# MCU_SCH.net
KiCad netlist of a schematic drawn in Altium Designer
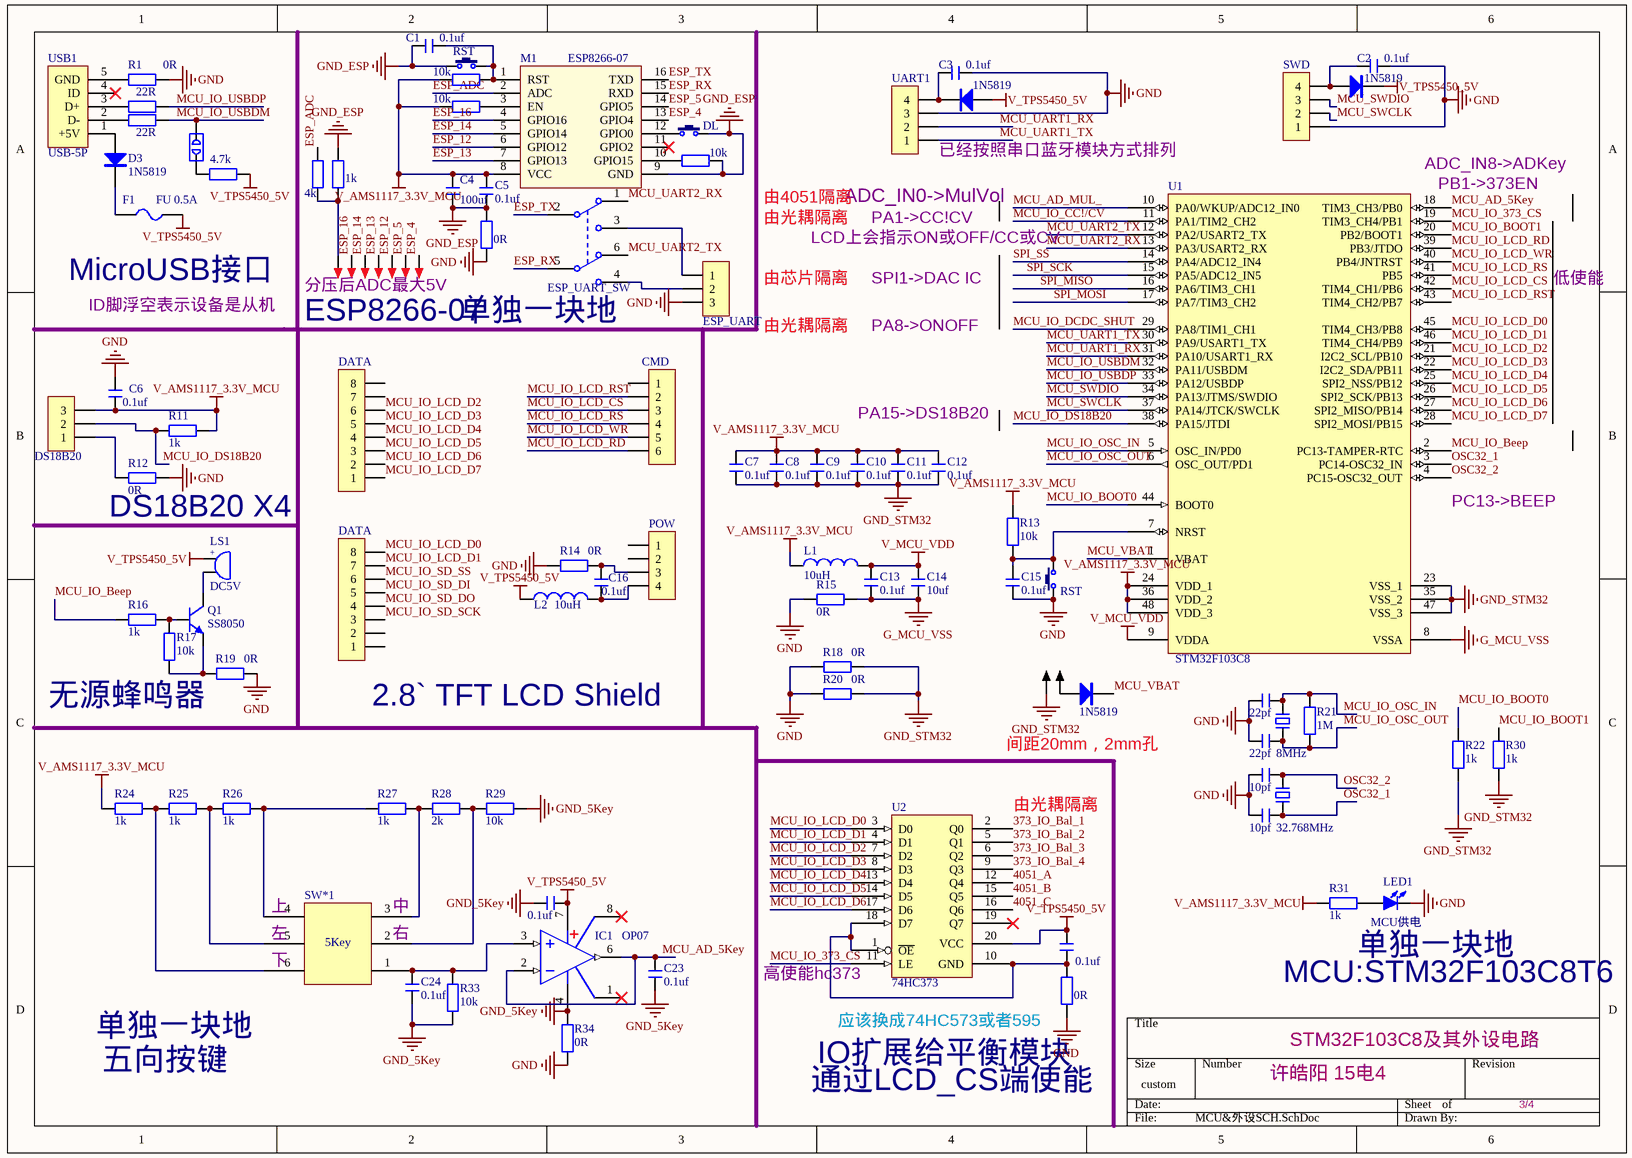
[diagram p0: MCU&外设SCH.SchDoc]

(export (version "E")
  (design (tool "Eeschema 10.0.6"))
  (components
    (comp (ref "*.")
      (value "CS")
      (footprint "HDR2.54-LI-1P")
      (description "探针焊盘")
      (libsource (lib "15.1 - 未分类器件") (part "CS"))
    )
    (comp (ref "*..")
      (value "CS")
      (footprint "HDR2.54-LI-1P")
      (description "探针焊盘")
      (libsource (lib "15.1 - 未分类器件") (part "CS"))
    )
    (comp (ref "C1")
      (value "0.1uf")
      (footprint "C 0805_M")
      (description "无极性贴片电容")
      (libsource (lib "3.1   - 电阻-电容-电感") (part "C"))
    )
    (comp (ref "C2")
      (value "0.1uf")
      (footprint "C 0805_M")
      (description "无极性贴片电容")
      (libsource (lib "3.1   - 电阻-电容-电感") (part "C"))
    )
    (comp (ref "C3")
      (value "0.1uf")
      (footprint "C 0805_M")
      (description "无极性贴片电容")
      (libsource (lib "3.1   - 电阻-电容-电感") (part "C"))
    )
    (comp (ref "C4")
      (value "100uf")
      (footprint "CD D(7343)")
      (description "无极性贴片电容")
      (libsource (lib "3.1   - 电阻-电容-电感") (part "C"))
    )
    (comp (ref "C5")
      (value "0.1uf")
      (footprint "C 0805_M")
      (description "无极性贴片电容")
      (libsource (lib "3.1   - 电阻-电容-电感") (part "C"))
    )
    (comp (ref "C6")
      (value "0.1uf")
      (footprint "C 0805_M")
      (description "无极性贴片电容")
      (libsource (lib "3.1   - 电阻-电容-电感") (part "C"))
    )
    (comp (ref "C7")
      (value "0.1uf")
      (footprint "C 0805_M")
      (description "无极性贴片电容")
      (libsource (lib "3.1   - 电阻-电容-电感") (part "C"))
    )
    (comp (ref "C8")
      (value "0.1uf")
      (footprint "C 0805_M")
      (description "无极性贴片电容")
      (libsource (lib "3.1   - 电阻-电容-电感") (part "C"))
    )
    (comp (ref "C9")
      (value "0.1uf")
      (footprint "C 0805_M")
      (description "无极性贴片电容")
      (libsource (lib "3.1   - 电阻-电容-电感") (part "C"))
    )
    (comp (ref "C10")
      (value "0.1uf")
      (footprint "C 0805_M")
      (description "无极性贴片电容")
      (libsource (lib "3.1   - 电阻-电容-电感") (part "C"))
    )
    (comp (ref "C11")
      (value "0.1uf")
      (footprint "C 0805_M")
      (description "无极性贴片电容")
      (libsource (lib "3.1   - 电阻-电容-电感") (part "C"))
    )
    (comp (ref "C12")
      (value "0.1uf")
      (footprint "C 0805_M")
      (description "无极性贴片电容")
      (libsource (lib "3.1   - 电阻-电容-电感") (part "C"))
    )
    (comp (ref "C13")
      (value "0.1uf")
      (footprint "C 0805_M")
      (description "无极性贴片电容")
      (libsource (lib "3.1   - 电阻-电容-电感") (part "C"))
    )
    (comp (ref "C14")
      (value "10uf")
      (footprint "C 0805_M")
      (description "无极性贴片电容")
      (libsource (lib "3.1   - 电阻-电容-电感") (part "C"))
    )
    (comp (ref "C15")
      (value "0.1uf")
      (footprint "C 0805_M")
      (description "无极性贴片电容")
      (libsource (lib "3.1   - 电阻-电容-电感") (part "C"))
    )
    (comp (ref "C16")
      (value "0.1uf")
      (footprint "C 0805_M")
      (description "无极性贴片电容")
      (libsource (lib "3.1   - 电阻-电容-电感") (part "C"))
    )
    (comp (ref "C17")
      (value "22pf")
      (footprint "C 0805_M")
      (description "无极性贴片电容")
      (libsource (lib "3.1   - 电阻-电容-电感") (part "C"))
    )
    (comp (ref "C18")
      (value "22pf")
      (footprint "C 0805_M")
      (description "无极性贴片电容")
      (libsource (lib "3.1   - 电阻-电容-电感") (part "C"))
    )
    (comp (ref "C19")
      (value "10pf")
      (footprint "C 0805_M")
      (description "无极性贴片电容")
      (libsource (lib "3.1   - 电阻-电容-电感") (part "C"))
    )
    (comp (ref "C20")
      (value "10pf")
      (footprint "C 0805_M")
      (description "无极性贴片电容")
      (libsource (lib "3.1   - 电阻-电容-电感") (part "C"))
    )
    (comp (ref "C21")
      (value "0.1uf")
      (footprint "C 0805_M")
      (description "无极性贴片电容")
      (libsource (lib "3.1   - 电阻-电容-电感") (part "C"))
    )
    (comp (ref "C22")
      (value "0.1uf")
      (footprint "C 0805_M")
      (description "无极性贴片电容")
      (libsource (lib "3.1   - 电阻-电容-电感") (part "C"))
    )
    (comp (ref "C23")
      (value "0.1uf")
      (footprint "C 0805_M")
      (description "无极性贴片电容")
      (libsource (lib "3.1   - 电阻-电容-电感") (part "C"))
    )
    (comp (ref "C24")
      (value "0.1uf")
      (footprint "C 0805_M")
      (description "无极性贴片电容")
      (libsource (lib "3.1   - 电阻-电容-电感") (part "C"))
    )
    (comp (ref "D1")
      (value "1N5819")
      (footprint "SOD-123")
      (description "肖特基二极管")
      (libsource (lib "8.1   - 二极管-整流桥") (part "1N5819"))
    )
    (comp (ref "D2")
      (value "1N5819")
      (footprint "SOD-123")
      (description "肖特基二极管")
      (libsource (lib "8.1   - 二极管-整流桥") (part "1N5819"))
    )
    (comp (ref "D2.")
      (value "1N5819")
      (footprint "SOD-123")
      (description "肖特基二极管")
      (libsource (lib "8.1   - 二极管-整流桥") (part "1N5819"))
    )
    (comp (ref "D3")
      (value "1N5819")
      (footprint "SOD-123")
      (description "肖特基二极管")
      (libsource (lib "8.1   - 二极管-整流桥") (part "1N5819"))
    )
    (comp (ref "DE1")
      (value "1")
      (footprint "DEBUG_B")
      (description "调试断点焊盘")
      (libsource (lib "15.1 - 未分类器件") (part "DEBUG"))
    )
    (comp (ref "F1")
      (value "FU 0.5A")
      (footprint "FU 1206")
      (description "贴片保险丝")
      (libsource (lib "10.1 - 保险丝-晶振") (part "FU"))
    )
    (comp (ref "IC1")
      (value "OP07")
      (footprint "SOP8_N")
      (description "单路精密运放")
      (libsource (lib "1.5   - 运放-功放") (part "OP07"))
    )
    (comp (ref "JP1")
      (value "SWD")
      (footprint "HDR2.54-LI-4P")
      (description "4P接插件")
      (libsource (lib "") (part "Header 4_1"))
    )
    (comp (ref "JP2")
      (value "UART1")
      (footprint "HDR2.54-LI-4P")
      (description "4P接插件")
      (libsource (lib "") (part "Header 4_1"))
    )
    (comp (ref "JP3")
      (value "ESP_UART")
      (footprint "HDR2.54-LI-3P")
      (description "3P接插件")
      (libsource (lib "") (part "Header 3_1"))
    )
    (comp (ref "JP4")
      (value "DS18B20")
      (footprint "HDR2.54-LI-3P")
      (description "3P接插件")
      (libsource (lib "4.6   - 接插件-脚距2.54") (part "Header 3"))
    )
    (comp (ref "JP5")
      (value "CMD")
      (footprint "HDR2.54-M-LI-6P")
      (description "6P接插件")
      (libsource (lib "4.6   - 接插件-脚距2.54") (part "Header 6"))
    )
    (comp (ref "JP6")
      (value "DATA")
      (footprint "HDR2.54-M-LI-8P")
      (description "8P接插件")
      (libsource (lib "4.6   - 接插件-脚距2.54") (part "Header 8"))
    )
    (comp (ref "JP6.")
      (value "DATA")
      (footprint "HDR2.54-M-LI-8P")
      (description "8P接插件")
      (libsource (lib "4.6   - 接插件-脚距2.54") (part "Header 8"))
    )
    (comp (ref "JP7")
      (value "POW")
      (footprint "HDR2.54-M-LI-4P")
      (description "4P接插件")
      (libsource (lib "4.6   - 接插件-脚距2.54") (part "Header 4"))
    )
    (comp (ref "L1")
      (value "10uH")
      (footprint "L 0805_M")
      (description "小功率贴片电感")
      (libsource (lib "3.1   - 电阻-电容-电感") (part "L"))
    )
    (comp (ref "L2")
      (value "10uH")
      (footprint "L 0805_M")
      (description "小功率贴片电感")
      (libsource (lib "3.1   - 电阻-电容-电感") (part "L"))
    )
    (comp (ref "LED1")
      (value "MCU供电")
      (footprint "LED 0805G")
      (description "贴片LED")
      (libsource (lib "9.1   - LED") (part "LED-SMD"))
    )
    (comp (ref "LS1")
      (value "DC5V")
      (footprint "BEEP 7.6X12X7.5")
      (description "蜂鸣器")
      (libsource (lib "15.1 - 未分类器件") (part "BEEP"))
    )
    (comp (ref "M1")
      (value "ESP8266-07")
      (footprint "ESP-07")
      (description "串口 WIFI模块，ESP-07")
      (libsource (lib "13.1 - 模块") (part "ESP8266-07"))
    )
    (comp (ref "Q1")
      (value "SS8050")
      (footprint "SOT23-3M")
      (description "高频放大-NPN型")
      (libsource (lib "6.2   - 三极管") (part "8050-SMD"))
    )
    (comp (ref "R1")
      (value "0R")
      (footprint "R 0805_M")
      (description "贴片电阻")
      (libsource (lib "3.1   - 电阻-电容-电感") (part "R"))
    )
    (comp (ref "R2")
      (value "10k")
      (footprint "R 0805_M")
      (description "贴片电阻")
      (libsource (lib "3.1   - 电阻-电容-电感") (part "R"))
    )
    (comp (ref "R3")
      (value "22R")
      (footprint "R 0805_M")
      (description "贴片电阻")
      (libsource (lib "3.1   - 电阻-电容-电感") (part "R"))
    )
    (comp (ref "R4")
      (value "10k")
      (footprint "R 0805_M")
      (description "贴片电阻")
      (libsource (lib "3.1   - 电阻-电容-电感") (part "R"))
    )
    (comp (ref "R5")
      (value "22R")
      (footprint "R 0805_M")
      (description "贴片电阻")
      (libsource (lib "3.1   - 电阻-电容-电感") (part "R"))
    )
    (comp (ref "R6")
      (value "10k")
      (footprint "R 0805_M")
      (description "贴片电阻")
      (libsource (lib "3.1   - 电阻-电容-电感") (part "R"))
    )
    (comp (ref "R7")
      (value "4.7k")
      (footprint "R 0805_M")
      (description "贴片电阻")
      (libsource (lib "3.1   - 电阻-电容-电感") (part "R"))
    )
    (comp (ref "R8")
      (value "4k")
      (footprint "R 0805_M")
      (description "贴片电阻")
      (libsource (lib "3.1   - 电阻-电容-电感") (part "R"))
    )
    (comp (ref "R9")
      (value "1k")
      (footprint "R 0805_M")
      (description "贴片电阻")
      (libsource (lib "3.1   - 电阻-电容-电感") (part "R"))
    )
    (comp (ref "R10")
      (value "0R")
      (footprint "R 0805_M")
      (description "贴片电阻")
      (libsource (lib "3.1   - 电阻-电容-电感") (part "R"))
    )
    (comp (ref "R11")
      (value "1k")
      (footprint "R 0805_M")
      (description "贴片电阻")
      (libsource (lib "3.1   - 电阻-电容-电感") (part "R"))
    )
    (comp (ref "R12")
      (value "0R")
      (footprint "R 0805_M")
      (description "贴片电阻")
      (libsource (lib "3.1   - 电阻-电容-电感") (part "R"))
    )
    (comp (ref "R13")
      (value "10k")
      (footprint "R 0805_M")
      (description "贴片电阻")
      (libsource (lib "3.1   - 电阻-电容-电感") (part "R"))
    )
    (comp (ref "R14")
      (value "0R")
      (footprint "R 0805_M")
      (description "贴片电阻")
      (libsource (lib "3.1   - 电阻-电容-电感") (part "R"))
    )
    (comp (ref "R15")
      (value "0R")
      (footprint "R 0805_M")
      (description "贴片电阻")
      (libsource (lib "3.1   - 电阻-电容-电感") (part "R"))
    )
    (comp (ref "R16")
      (value "1k")
      (footprint "R 0805_M")
      (description "贴片电阻")
      (libsource (lib "3.1   - 电阻-电容-电感") (part "R"))
    )
    (comp (ref "R17")
      (value "10k")
      (footprint "R 0805_M")
      (description "贴片电阻")
      (libsource (lib "3.1   - 电阻-电容-电感") (part "R"))
    )
    (comp (ref "R18")
      (value "0R")
      (footprint "R 0805_M")
      (description "贴片电阻")
      (libsource (lib "3.1   - 电阻-电容-电感") (part "R"))
    )
    (comp (ref "R19")
      (value "0R")
      (footprint "R 0805_M")
      (description "贴片电阻")
      (libsource (lib "3.1   - 电阻-电容-电感") (part "R"))
    )
    (comp (ref "R20")
      (value "0R")
      (footprint "R 0805_M")
      (description "贴片电阻")
      (libsource (lib "3.1   - 电阻-电容-电感") (part "R"))
    )
    (comp (ref "R21")
      (value "1M")
      (footprint "R 0805_M")
      (description "贴片电阻")
      (libsource (lib "3.1   - 电阻-电容-电感") (part "R"))
    )
    (comp (ref "R22")
      (value "1k")
      (footprint "R 0805_M")
      (description "贴片电阻")
      (libsource (lib "3.1   - 电阻-电容-电感") (part "R"))
    )
    (comp (ref "R24")
      (value "1k")
      (footprint "R 0805_M")
      (description "贴片电阻")
      (libsource (lib "3.1   - 电阻-电容-电感") (part "R"))
    )
    (comp (ref "R25")
      (value "1k")
      (footprint "R 0805_M")
      (description "贴片电阻")
      (libsource (lib "3.1   - 电阻-电容-电感") (part "R"))
    )
    (comp (ref "R26")
      (value "1k")
      (footprint "R 0805_M")
      (description "贴片电阻")
      (libsource (lib "3.1   - 电阻-电容-电感") (part "R"))
    )
    (comp (ref "R27")
      (value "1k")
      (footprint "R 0805_M")
      (description "贴片电阻")
      (libsource (lib "3.1   - 电阻-电容-电感") (part "R"))
    )
    (comp (ref "R28")
      (value "2k")
      (footprint "R 0805_M")
      (description "贴片电阻")
      (libsource (lib "3.1   - 电阻-电容-电感") (part "R"))
    )
    (comp (ref "R29")
      (value "10k")
      (footprint "R 0805_M")
      (description "贴片电阻")
      (libsource (lib "3.1   - 电阻-电容-电感") (part "R"))
    )
    (comp (ref "R30")
      (value "1k")
      (footprint "R 0805_M")
      (description "贴片电阻")
      (libsource (lib "3.1   - 电阻-电容-电感") (part "R"))
    )
    (comp (ref "R31")
      (value "1k")
      (footprint "R 0805_M")
      (description "贴片电阻")
      (libsource (lib "3.1   - 电阻-电容-电感") (part "R"))
    )
    (comp (ref "R32")
      (value "0R")
      (footprint "R 0805_M")
      (description "贴片电阻")
      (libsource (lib "3.1   - 电阻-电容-电感") (part "R"))
    )
    (comp (ref "R33")
      (value "10k")
      (footprint "R 0805_M")
      (description "贴片电阻")
      (libsource (lib "3.1   - 电阻-电容-电感") (part "R"))
    )
    (comp (ref "R34")
      (value "0R")
      (footprint "R 0805_M")
      (description "贴片电阻")
      (libsource (lib "3.1   - 电阻-电容-电感") (part "R"))
    )
    (comp (ref "S.")
      (value "ESP_UART_SW")
      (footprint "SK-22D02")
      (description "2路波动开关")
      (libsource (lib "5.1   - 按键-开关") (part "SSW-2P"))
    )
    (comp (ref "SW*1")
      (value "5Key")
      (footprint "TSW 10x10x9-5Key-LS")
      (libsource (lib "IC_temp") (part "6"))
    )
    (comp (ref "SW1")
      (value "RST")
      (footprint "TSW SMD-3*6*2.5")
      (description "3x6轻触开关")
      (libsource (lib "5.1   - 按键-开关") (part "TSW 3x6"))
    )
    (comp (ref "SW2")
      (value "DL")
      (footprint "TSW SMD-3*6*2.5")
      (description "3x6轻触开关")
      (libsource (lib "5.1   - 按键-开关") (part "TSW 3x6"))
    )
    (comp (ref "SW3")
      (value "RST")
      (footprint "TSW SMD-3*6*2.5")
      (description "3x6轻触开关")
      (libsource (lib "") (part "TSW 3x6_1"))
    )
    (comp (ref "TP1")
      (value "..")
      (footprint "TEST 1")
      (description "测试点")
      (libsource (lib "15.1 - 未分类器件") (part "TEST"))
    )
    (comp (ref "TP2")
      (value "..")
      (footprint "TEST 1")
      (description "测试点")
      (libsource (lib "15.1 - 未分类器件") (part "TEST"))
    )
    (comp (ref "TP3")
      (value "..")
      (footprint "TEST 1")
      (description "测试点")
      (libsource (lib "15.1 - 未分类器件") (part "TEST"))
    )
    (comp (ref "TP4")
      (value "..")
      (footprint "TEST 1")
      (description "测试点")
      (libsource (lib "15.1 - 未分类器件") (part "TEST"))
    )
    (comp (ref "TP5")
      (value "..")
      (footprint "TEST 1")
      (description "测试点")
      (libsource (lib "15.1 - 未分类器件") (part "TEST"))
    )
    (comp (ref "TP6")
      (value "..")
      (footprint "TEST 1")
      (description "测试点")
      (libsource (lib "15.1 - 未分类器件") (part "TEST"))
    )
    (comp (ref "TP7")
      (value "..")
      (footprint "TEST 1")
      (description "测试点")
      (libsource (lib "15.1 - 未分类器件") (part "TEST"))
    )
    (comp (ref "U1")
      (value "STM32F103C8")
      (footprint "LQFP48 7X7_N")
      (description "Flaah:64/RAM:20/IO:36")
      (libsource (lib "2.1   - STM32系列单片机") (part "STM32F103C8"))
    )
    (comp (ref "U2") (value "74HC373") (footprint "SOP20_N") (libsource (lib "逻辑门器件") (part "74HC373")))
    (comp (ref "USB1")
      (value "USB-5P")
      (footprint "USB-MICRO_E")
      (description "微型USB母座")
      (libsource (lib "4.1   - 接口类") (part "USB-5P"))
    )
    (comp (ref "X1")
      (value "8MHz")
      (footprint "OSC HC-49S")
      (description "2脚无源脚晶振")
      (libsource (lib "10.1 - 保险丝-晶振") (part "XTAL-2P"))
    )
    (comp (ref "X2")
      (value "32.768MHz")
      (footprint "OSC-3x8-LI")
      (description "2脚无源脚晶振")
      (libsource (lib "10.1 - 保险丝-晶振") (part "XTAL-2P"))
    )
  )
  (nets
    (net (code "1") (name "/373_IO_Bal_1") (class "Default")
      (node (ref "U2") (pin "2") (pinfunction "Q0_2") (pintype "tri_state"))
    )
    (net (code "2") (name "/373_IO_Bal_2") (class "Default")
      (node (ref "U2") (pin "5") (pinfunction "Q1_5") (pintype "tri_state"))
    )
    (net (code "3") (name "/373_IO_Bal_3") (class "Default")
      (node (ref "U2") (pin "6") (pinfunction "Q2_6") (pintype "tri_state"))
    )
    (net (code "4") (name "/373_IO_Bal_4") (class "Default")
      (node (ref "U2") (pin "9") (pinfunction "Q3_9") (pintype "tri_state"))
    )
    (net (code "5") (name "/4051_A") (class "Default")
      (node (ref "U2") (pin "12") (pinfunction "Q4_12") (pintype "tri_state"))
    )
    (net (code "6") (name "/4051_B") (class "Default")
      (node (ref "U2") (pin "15") (pinfunction "Q5_15") (pintype "tri_state"))
    )
    (net (code "7") (name "/4051_C") (class "Default")
      (node (ref "U2") (pin "16") (pinfunction "Q6_16") (pintype "tri_state"))
    )
    (net (code "8") (name "/ESP_4") (class "Default")
      (node (ref "M1") (pin "13") (pinfunction "GPIO4_13") (pintype "passive"))
      (node (ref "TP7") (pin "1") (pinfunction "1_1") (pintype "passive"))
    )
    (net (code "9") (name "/ESP_5") (class "Default")
      (node (ref "M1") (pin "14") (pinfunction "GPIO5_14") (pintype "passive"))
      (node (ref "TP6") (pin "1") (pinfunction "1_1") (pintype "passive"))
    )
    (net (code "10") (name "/ESP_12") (class "Default")
      (node (ref "M1") (pin "6") (pinfunction "GPIO12_6") (pintype "passive"))
      (node (ref "TP5") (pin "1") (pinfunction "1_1") (pintype "passive"))
    )
    (net (code "11") (name "/ESP_13") (class "Default")
      (node (ref "M1") (pin "7") (pinfunction "GPIO13_7") (pintype "passive"))
      (node (ref "TP4") (pin "1") (pinfunction "1_1") (pintype "passive"))
    )
    (net (code "12") (name "/ESP_14") (class "Default")
      (node (ref "M1") (pin "5") (pinfunction "GPIO14_5") (pintype "passive"))
      (node (ref "TP3") (pin "1") (pinfunction "1_1") (pintype "passive"))
    )
    (net (code "13") (name "/ESP_16") (class "Default")
      (node (ref "M1") (pin "4") (pinfunction "GPIO16_4") (pintype "passive"))
      (node (ref "TP2") (pin "1") (pinfunction "1_1") (pintype "passive"))
    )
    (net (code "14") (name "/ESP_ADC") (class "Default")
      (node (ref "M1") (pin "2") (pinfunction "ADC_2") (pintype "passive"))
      (node (ref "R8") (pin "2") (pinfunction "2_2") (pintype "passive"))
    )
    (net (code "15") (name "/ESP_RX") (class "Default")
      (node (ref "M1") (pin "15") (pinfunction "RXD_15") (pintype "passive"))
      (node (ref "S.") (pin "5") (pinfunction "5_5") (pintype "passive"))
    )
    (net (code "16") (name "/ESP_TX") (class "Default")
      (node (ref "M1") (pin "16") (pinfunction "TXD_16") (pintype "passive"))
      (node (ref "S.") (pin "2") (pinfunction "2_2") (pintype "passive"))
    )
    (net (code "17") (name "/MCU_AD_5Key") (class "Default")
      (node (ref "C23") (pin "2") (pinfunction "2_2") (pintype "passive"))
      (node (ref "IC1") (pin "2") (pinfunction "IN-_2") (pintype "input"))
      (node (ref "IC1") (pin "6") (pinfunction "OUT_6") (pintype "output"))
      (node (ref "U1") (pin "18") (pinfunction "TIM3_CH3/PB0_18") (pintype "bidirectional"))
    )
    (net (code "18") (name "/MCU_AD_MUL_") (class "Default")
      (node (ref "U1") (pin "10") (pinfunction "PA0/WKUP/ADC12_IN0_10") (pintype "bidirectional"))
    )
    (net (code "19") (name "/MCU_IO_373_CS") (class "Default")
      (node (ref "U1") (pin "19") (pinfunction "TIM3_CH4/PB1_19") (pintype "bidirectional"))
      (node (ref "U2") (pin "11") (pinfunction "LE_11") (pintype "input"))
    )
    (net (code "20") (name "/MCU_IO_BOOT0") (class "Default")
      (node (ref "R22") (pin "2") (pinfunction "2_2") (pintype "passive"))
      (node (ref "U1") (pin "44") (pinfunction "BOOT0_44") (pintype "input"))
    )
    (net (code "21") (name "/MCU_IO_BOOT1") (class "Default")
      (node (ref "R30") (pin "2") (pinfunction "2_2") (pintype "passive"))
      (node (ref "U1") (pin "20") (pinfunction "PB2/BOOT1_20") (pintype "bidirectional"))
    )
    (net (code "22") (name "/MCU_IO_Beep") (class "Default")
      (node (ref "R16") (pin "2") (pinfunction "2_2") (pintype "passive"))
      (node (ref "U1") (pin "2") (pinfunction "PC13-TAMPER-RTC_2") (pintype "bidirectional"))
    )
    (net (code "23") (name "/MCU_IO_CC!{slash}CV") (class "Default")
      (node (ref "U1") (pin "11") (pinfunction "PA1/TIM2_CH2_11") (pintype "bidirectional"))
    )
    (net (code "24") (name "/MCU_IO_DCDC_SHUT") (class "Default")
      (node (ref "U1") (pin "29") (pinfunction "PA8/TIM1_CH1_29") (pintype "bidirectional"))
    )
    (net (code "25") (name "/MCU_IO_DS18B20") (class "Default")
      (node (ref "JP4") (pin "2") (pinfunction "2_2") (pintype "passive"))
      (node (ref "R11") (pin "1") (pinfunction "1_1") (pintype "passive"))
      (node (ref "U1") (pin "38") (pinfunction "PA15/JTDI_38") (pintype "bidirectional"))
    )
    (net (code "26") (name "/MCU_IO_LCD_CS") (class "Default")
      (node (ref "JP5") (pin "3") (pinfunction "3_3") (pintype "passive"))
      (node (ref "U1") (pin "42") (pinfunction "TIM4_CH1/PB6_42") (pintype "bidirectional"))
    )
    (net (code "27") (name "/MCU_IO_LCD_D0") (class "Default")
      (node (ref "JP6.") (pin "8") (pinfunction "8_8") (pintype "passive"))
      (node (ref "U1") (pin "45") (pinfunction "TIM4_CH3/PB8_45") (pintype "bidirectional"))
      (node (ref "U2") (pin "3") (pinfunction "D0_3") (pintype "input"))
    )
    (net (code "28") (name "/MCU_IO_LCD_D1") (class "Default")
      (node (ref "JP6.") (pin "7") (pinfunction "7_7") (pintype "passive"))
      (node (ref "U1") (pin "46") (pinfunction "TIM4_CH4/PB9_46") (pintype "bidirectional"))
      (node (ref "U2") (pin "4") (pinfunction "D1_4") (pintype "input"))
    )
    (net (code "29") (name "/MCU_IO_LCD_D2") (class "Default")
      (node (ref "JP6") (pin "6") (pinfunction "6_6") (pintype "passive"))
      (node (ref "U1") (pin "21") (pinfunction "I2C2_SCL/PB10_21") (pintype "bidirectional"))
      (node (ref "U2") (pin "7") (pinfunction "D2_7") (pintype "input"))
    )
    (net (code "30") (name "/MCU_IO_LCD_D3") (class "Default")
      (node (ref "JP6") (pin "5") (pinfunction "5_5") (pintype "passive"))
      (node (ref "U1") (pin "22") (pinfunction "I2C2_SDA/PB11_22") (pintype "bidirectional"))
      (node (ref "U2") (pin "8") (pinfunction "D3_8") (pintype "input"))
    )
    (net (code "31") (name "/MCU_IO_LCD_D4") (class "Default")
      (node (ref "JP6") (pin "4") (pinfunction "4_4") (pintype "passive"))
      (node (ref "U1") (pin "25") (pinfunction "SPI2_NSS/PB12_25") (pintype "bidirectional"))
      (node (ref "U2") (pin "13") (pinfunction "D4_13") (pintype "input"))
    )
    (net (code "32") (name "/MCU_IO_LCD_D5") (class "Default")
      (node (ref "JP6") (pin "3") (pinfunction "3_3") (pintype "passive"))
      (node (ref "U1") (pin "26") (pinfunction "SPI2_SCK/PB13_26") (pintype "bidirectional"))
      (node (ref "U2") (pin "14") (pinfunction "D5_14") (pintype "input"))
    )
    (net (code "33") (name "/MCU_IO_LCD_D6") (class "Default")
      (node (ref "JP6") (pin "2") (pinfunction "2_2") (pintype "passive"))
      (node (ref "U1") (pin "27") (pinfunction "SPI2_MISO/PB14_27") (pintype "bidirectional"))
      (node (ref "U2") (pin "17") (pinfunction "D6_17") (pintype "input"))
    )
    (net (code "34") (name "/MCU_IO_LCD_D7") (class "Default")
      (node (ref "JP6") (pin "1") (pinfunction "1_1") (pintype "passive"))
      (node (ref "U1") (pin "28") (pinfunction "SPI2_MOSI/PB15_28") (pintype "bidirectional"))
    )
    (net (code "35") (name "/MCU_IO_LCD_RD") (class "Default")
      (node (ref "JP5") (pin "6") (pinfunction "6_6") (pintype "passive"))
      (node (ref "U1") (pin "39") (pinfunction "PB3/JTDO_39") (pintype "bidirectional"))
    )
    (net (code "36") (name "/MCU_IO_LCD_RS") (class "Default")
      (node (ref "JP5") (pin "4") (pinfunction "4_4") (pintype "passive"))
      (node (ref "U1") (pin "41") (pinfunction "PB5_41") (pintype "bidirectional"))
    )
    (net (code "37") (name "/MCU_IO_LCD_RST") (class "Default")
      (node (ref "JP5") (pin "2") (pinfunction "2_2") (pintype "passive"))
      (node (ref "U1") (pin "43") (pinfunction "TIM4_CH2/PB7_43") (pintype "bidirectional"))
    )
    (net (code "38") (name "/MCU_IO_LCD_WR") (class "Default")
      (node (ref "JP5") (pin "5") (pinfunction "5_5") (pintype "passive"))
      (node (ref "U1") (pin "40") (pinfunction "PB4/JNTRST_40") (pintype "bidirectional"))
    )
    (net (code "39") (name "/MCU_IO_OSC_IN") (class "Default")
      (node (ref "C17") (pin "1") (pinfunction "1_1") (pintype "passive"))
      (node (ref "R21") (pin "1") (pinfunction "1_1") (pintype "passive"))
      (node (ref "U1") (pin "5") (pinfunction "OSC_IN/PD0_5") (pintype "input"))
      (node (ref "X1") (pin "2") (pinfunction "2_2") (pintype "passive"))
    )
    (net (code "40") (name "/MCU_IO_OSC_OUT") (class "Default")
      (node (ref "C18") (pin "1") (pinfunction "1_1") (pintype "passive"))
      (node (ref "R21") (pin "2") (pinfunction "2_2") (pintype "passive"))
      (node (ref "U1") (pin "6") (pinfunction "OSC_OUT/PD1_6") (pintype "output"))
      (node (ref "X1") (pin "1") (pinfunction "1_1") (pintype "passive"))
    )
    (net (code "41") (name "/MCU_IO_SD_DI") (class "Default")
      (node (ref "JP6.") (pin "5") (pinfunction "5_5") (pintype "passive"))
    )
    (net (code "42") (name "/MCU_IO_SD_DO") (class "Default")
      (node (ref "JP6.") (pin "4") (pinfunction "4_4") (pintype "passive"))
    )
    (net (code "43") (name "/MCU_IO_SD_SCK") (class "Default")
      (node (ref "JP6.") (pin "3") (pinfunction "3_3") (pintype "passive"))
    )
    (net (code "44") (name "/MCU_IO_SD_SS") (class "Default")
      (node (ref "JP6.") (pin "6") (pinfunction "6_6") (pintype "passive"))
    )
    (net (code "45") (name "/MCU_IO_USBDM") (class "Default")
      (node (ref "DE1") (pin "2") (pinfunction "2_2") (pintype "passive"))
      (node (ref "R5") (pin "1") (pinfunction "1_1") (pintype "passive"))
      (node (ref "U1") (pin "32") (pinfunction "PA11/USBDM_32") (pintype "bidirectional"))
    )
    (net (code "46") (name "/MCU_IO_USBDP") (class "Default")
      (node (ref "R3") (pin "1") (pinfunction "1_1") (pintype "passive"))
      (node (ref "U1") (pin "33") (pinfunction "PA12/USBDP_33") (pintype "bidirectional"))
    )
    (net (code "47") (name "/MCU_SWCLK") (class "Default")
      (node (ref "JP1") (pin "2") (pinfunction "2_2") (pintype "passive"))
      (node (ref "U1") (pin "37") (pinfunction "PA14/JTCK/SWCLK_37") (pintype "bidirectional"))
    )
    (net (code "48") (name "/MCU_SWDIO") (class "Default")
      (node (ref "JP1") (pin "3") (pinfunction "3_3") (pintype "passive"))
      (node (ref "U1") (pin "34") (pinfunction "PA13/JTMS/SWDIO_34") (pintype "bidirectional"))
    )
    (net (code "49") (name "/MCU_UART1_RX") (class "Default")
      (node (ref "JP2") (pin "2") (pinfunction "2_2") (pintype "passive"))
      (node (ref "U1") (pin "31") (pinfunction "PA10/USART1_RX_31") (pintype "bidirectional"))
    )
    (net (code "50") (name "/MCU_UART1_TX") (class "Default")
      (node (ref "JP2") (pin "1") (pinfunction "1_1") (pintype "passive"))
      (node (ref "U1") (pin "30") (pinfunction "PA9/USART1_TX_30") (pintype "bidirectional"))
    )
    (net (code "51") (name "/MCU_UART2_RX") (class "Default")
      (node (ref "S.") (pin "1") (pinfunction "1_1") (pintype "passive"))
      (node (ref "U1") (pin "13") (pinfunction "PA3/USART2_RX_13") (pintype "bidirectional"))
    )
    (net (code "52") (name "/MCU_UART2_TX") (class "Default")
      (node (ref "S.") (pin "6") (pinfunction "6_6") (pintype "passive"))
      (node (ref "U1") (pin "12") (pinfunction "PA2/USART2_TX_12") (pintype "bidirectional"))
    )
    (net (code "53") (name "/MCU_VBAT") (class "Default")
      (node (ref "D2.") (pin "2") (pinfunction "K_2") (pintype "passive"))
      (node (ref "U1") (pin "1") (pinfunction "VBAT_1") (pintype "power_in"))
    )
    (net (code "54") (name "/OSC32_1") (class "Default")
      (node (ref "C20") (pin "1") (pinfunction "1_1") (pintype "passive"))
      (node (ref "U1") (pin "3") (pinfunction "PC14-OSC32_IN_3") (pintype "bidirectional"))
      (node (ref "X2") (pin "1") (pinfunction "1_1") (pintype "passive"))
    )
    (net (code "55") (name "/OSC32_2") (class "Default")
      (node (ref "C19") (pin "1") (pinfunction "1_1") (pintype "passive"))
      (node (ref "U1") (pin "4") (pinfunction "PC15-OSC32_OUT_4") (pintype "bidirectional"))
      (node (ref "X2") (pin "2") (pinfunction "2_2") (pintype "passive"))
    )
    (net (code "56") (name "/SPI_MISO") (class "Default")
      (node (ref "U1") (pin "16") (pinfunction "PA6/TIM3_CH1_16") (pintype "bidirectional"))
    )
    (net (code "57") (name "/SPI_MOSI") (class "Default")
      (node (ref "U1") (pin "17") (pinfunction "PA7/TIM3_CH2_17") (pintype "bidirectional"))
    )
    (net (code "58") (name "/SPI_SCK") (class "Default")
      (node (ref "U1") (pin "15") (pinfunction "PA5/ADC12_IN5_15") (pintype "bidirectional"))
    )
    (net (code "59") (name "/SPI_SS") (class "Default")
      (node (ref "U1") (pin "14") (pinfunction "PA4/ADC12_IN4_14") (pintype "bidirectional"))
    )
    (net (code "60") (name "GND") (class "Default")
      (node (ref "C15") (pin "1") (pinfunction "1_1") (pintype "passive"))
      (node (ref "C17") (pin "2") (pinfunction "2_2") (pintype "passive"))
      (node (ref "C18") (pin "2") (pinfunction "2_2") (pintype "passive"))
      (node (ref "C19") (pin "2") (pinfunction "2_2") (pintype "passive"))
      (node (ref "C2") (pin "2") (pinfunction "2_2") (pintype "passive"))
      (node (ref "C20") (pin "2") (pinfunction "2_2") (pintype "passive"))
      (node (ref "C3") (pin "2") (pinfunction "2_2") (pintype "passive"))
      (node (ref "C6") (pin "2") (pinfunction "2_2") (pintype "passive"))
      (node (ref "JP1") (pin "1") (pinfunction "1_1") (pintype "passive"))
      (node (ref "JP2") (pin "3") (pinfunction "3_3") (pintype "passive"))
      (node (ref "JP3") (pin "3") (pinfunction "3_3") (pintype "passive"))
      (node (ref "LED1") (pin "2") (pinfunction "K_2") (pintype "passive"))
      (node (ref "R1") (pin "1") (pinfunction "1_1") (pintype "passive"))
      (node (ref "R10") (pin "2") (pinfunction "2_2") (pintype "passive"))
      (node (ref "R12") (pin "1") (pinfunction "1_1") (pintype "passive"))
      (node (ref "R14") (pin "1") (pinfunction "1_1") (pintype "passive"))
      (node (ref "R15") (pin "2") (pinfunction "2_2") (pintype "passive"))
      (node (ref "R18") (pin "1") (pinfunction "1_1") (pintype "passive"))
      (node (ref "R19") (pin "2") (pinfunction "2_2") (pintype "passive"))
      (node (ref "R20") (pin "1") (pinfunction "1_1") (pintype "passive"))
      (node (ref "R32") (pin "2") (pinfunction "2_2") (pintype "passive"))
      (node (ref "R34") (pin "2") (pinfunction "2_2") (pintype "passive"))
      (node (ref "SW3") (pin "1") (pinfunction "1_1") (pintype "passive"))
    )
    (net (code "61") (name "GND_5Key") (class "Default")
      (node (ref "C21") (pin "1") (pinfunction "1_1") (pintype "passive"))
      (node (ref "C23") (pin "1") (pinfunction "1_1") (pintype "passive"))
      (node (ref "C24") (pin "1") (pinfunction "1_1") (pintype "passive"))
      (node (ref "IC1") (pin "4") (pinfunction "V-_4") (pintype "power_in"))
      (node (ref "R29") (pin "1") (pinfunction "1_1") (pintype "passive"))
      (node (ref "R33") (pin "1") (pinfunction "1_1") (pintype "passive"))
      (node (ref "R34") (pin "1") (pinfunction "1_1") (pintype "passive"))
    )
    (net (code "62") (name "GND_ESP") (class "Default")
      (node (ref "C1") (pin "2") (pinfunction "2_2") (pintype "passive"))
      (node (ref "C4") (pin "2") (pinfunction "2_2") (pintype "passive"))
      (node (ref "C5") (pin "1") (pinfunction "1_1") (pintype "passive"))
      (node (ref "M1") (pin "9") (pinfunction "GND_9") (pintype "passive"))
      (node (ref "R10") (pin "1") (pinfunction "1_1") (pintype "passive"))
      (node (ref "R6") (pin "2") (pinfunction "2_2") (pintype "passive"))
      (node (ref "R9") (pin "2") (pinfunction "2_2") (pintype "passive"))
      (node (ref "SW1") (pin "1") (pinfunction "1_1") (pintype "passive"))
      (node (ref "SW2") (pin "2") (pinfunction "2_2") (pintype "passive"))
    )
    (net (code "63") (name "GND_STM32") (class "Default")
      (node (ref "*.") (pin "1") (pinfunction "1_1") (pintype "passive"))
      (node (ref "C10") (pin "1") (pinfunction "1_1") (pintype "passive"))
      (node (ref "C11") (pin "1") (pinfunction "1_1") (pintype "passive"))
      (node (ref "C12") (pin "1") (pinfunction "1_1") (pintype "passive"))
      (node (ref "C7") (pin "1") (pinfunction "1_1") (pintype "passive"))
      (node (ref "C8") (pin "1") (pinfunction "1_1") (pintype "passive"))
      (node (ref "C9") (pin "1") (pinfunction "1_1") (pintype "passive"))
      (node (ref "R18") (pin "2") (pinfunction "2_2") (pintype "passive"))
      (node (ref "R20") (pin "2") (pinfunction "2_2") (pintype "passive"))
      (node (ref "R22") (pin "1") (pinfunction "1_1") (pintype "passive"))
      (node (ref "R30") (pin "1") (pinfunction "1_1") (pintype "passive"))
      (node (ref "U1") (pin "23") (pinfunction "VSS_1_23") (pintype "power_in"))
      (node (ref "U1") (pin "35") (pinfunction "VSS_2_35") (pintype "power_in"))
      (node (ref "U1") (pin "47") (pinfunction "VSS_3_47") (pintype "power_in"))
    )
    (net (code "64") (name "G_MCU_VSS") (class "Default")
      (node (ref "C13") (pin "1") (pinfunction "1_1") (pintype "passive"))
      (node (ref "C14") (pin "1") (pinfunction "1_1") (pintype "passive"))
      (node (ref "R15") (pin "1") (pinfunction "1_1") (pintype "passive"))
      (node (ref "U1") (pin "8") (pinfunction "VSSA_8") (pintype "power_in"))
    )
    (net (code "65") (name "Net-(C16-Pad1)") (class "Default")
      (node (ref "C16") (pin "1") (pinfunction "1_1") (pintype "passive"))
      (node (ref "JP7") (pin "4") (pinfunction "4_4") (pintype "passive"))
      (node (ref "L2") (pin "2") (pinfunction "2_2") (pintype "passive"))
    )
    (net (code "66") (name "Net-(C16-Pad2)") (class "Default")
      (node (ref "C16") (pin "2") (pinfunction "2_2") (pintype "passive"))
      (node (ref "JP7") (pin "3") (pinfunction "3_3") (pintype "passive"))
      (node (ref "R14") (pin "2") (pinfunction "2_2") (pintype "passive"))
    )
    (net (code "67") (name "Net-(D1-A)") (class "Default")
      (node (ref "C2") (pin "1") (pinfunction "1_1") (pintype "passive"))
      (node (ref "D1") (pin "1") (pinfunction "A_1") (pintype "passive"))
      (node (ref "JP1") (pin "4") (pinfunction "4_4") (pintype "passive"))
    )
    (net (code "68") (name "Net-(D2-K)") (class "Default")
      (node (ref "C3") (pin "1") (pinfunction "1_1") (pintype "passive"))
      (node (ref "D2") (pin "2") (pinfunction "K_2") (pintype "passive"))
      (node (ref "JP2") (pin "4") (pinfunction "4_4") (pintype "passive"))
    )
    (net (code "69") (name "Net-(D2.-A)") (class "Default")
      (node (ref "*..") (pin "1") (pinfunction "1_1") (pintype "passive"))
      (node (ref "D2.") (pin "1") (pinfunction "A_1") (pintype "passive"))
    )
    (net (code "70") (name "Net-(D3-A)") (class "Default")
      (node (ref "D3") (pin "1") (pinfunction "A_1") (pintype "passive"))
      (node (ref "USB1") (pin "1") (pinfunction "+5V_1") (pintype "passive"))
    )
    (net (code "71") (name "Net-(D3-K)") (class "Default")
      (node (ref "D3") (pin "2") (pinfunction "K_2") (pintype "passive"))
      (node (ref "F1") (pin "1") (pinfunction "1_1") (pintype "passive"))
    )
    (net (code "72") (name "Net-(DE1-Pad1)") (class "Default")
      (node (ref "DE1") (pin "1") (pinfunction "1_1") (pintype "passive"))
      (node (ref "R7") (pin "1") (pinfunction "1_1") (pintype "passive"))
    )
    (net (code "73") (name "Net-(IC1-IN+)") (class "Default")
      (node (ref "C24") (pin "2") (pinfunction "2_2") (pintype "passive"))
      (node (ref "IC1") (pin "3") (pinfunction "IN+_3") (pintype "input"))
      (node (ref "R33") (pin "2") (pinfunction "2_2") (pintype "passive"))
      (node (ref "SW*1") (pin "1") (pinfunction "1_1") (pintype "passive"))
    )
    (net (code "74") (name "Net-(JP3-Pad1)") (class "Default")
      (node (ref "JP3") (pin "1") (pinfunction "1_1") (pintype "passive"))
      (node (ref "S.") (pin "3") (pinfunction "3_3") (pintype "passive"))
    )
    (net (code "75") (name "Net-(JP3-Pad2)") (class "Default")
      (node (ref "JP3") (pin "2") (pinfunction "2_2") (pintype "passive"))
      (node (ref "S.") (pin "4") (pinfunction "4_4") (pintype "passive"))
    )
    (net (code "76") (name "Net-(JP4-Pad1)") (class "Default")
      (node (ref "JP4") (pin "1") (pinfunction "1_1") (pintype "passive"))
      (node (ref "R12") (pin "2") (pinfunction "2_2") (pintype "passive"))
    )
    (net (code "77") (name "Net-(LED1-A)") (class "Default")
      (node (ref "LED1") (pin "1") (pinfunction "A_1") (pintype "passive"))
      (node (ref "R31") (pin "2") (pinfunction "2_2") (pintype "passive"))
    )
    (net (code "78") (name "Net-(M1-EN)") (class "Default")
      (node (ref "M1") (pin "3") (pinfunction "EN_3") (pintype "passive"))
      (node (ref "R4") (pin "2") (pinfunction "2_2") (pintype "passive"))
    )
    (net (code "79") (name "Net-(M1-GPIO0)") (class "Default")
      (node (ref "M1") (pin "12") (pinfunction "GPIO0_12") (pintype "passive"))
      (node (ref "SW2") (pin "1") (pinfunction "1_1") (pintype "passive"))
    )
    (net (code "80") (name "Net-(M1-GPIO15)") (class "Default")
      (node (ref "M1") (pin "10") (pinfunction "GPIO15_10") (pintype "passive"))
      (node (ref "R6") (pin "1") (pinfunction "1_1") (pintype "passive"))
    )
    (net (code "81") (name "Net-(M1-RST)") (class "Default")
      (node (ref "C1") (pin "1") (pinfunction "1_1") (pintype "passive"))
      (node (ref "M1") (pin "1") (pinfunction "RST_1") (pintype "passive"))
      (node (ref "R2") (pin "2") (pinfunction "2_2") (pintype "passive"))
      (node (ref "SW1") (pin "2") (pinfunction "2_2") (pintype "passive"))
    )
    (net (code "82") (name "Net-(Q1-B)") (class "Default")
      (node (ref "Q1") (pin "1") (pinfunction "B_1") (pintype "passive"))
      (node (ref "R16") (pin "1") (pinfunction "1_1") (pintype "passive"))
      (node (ref "R17") (pin "1") (pinfunction "1_1") (pintype "passive"))
    )
    (net (code "83") (name "Net-(Q1-C)") (class "Default")
      (node (ref "LS1") (pin "2") (pinfunction "2_2") (pintype "passive"))
      (node (ref "Q1") (pin "3") (pinfunction "C_3") (pintype "passive"))
    )
    (net (code "84") (name "Net-(Q1-E)") (class "Default")
      (node (ref "Q1") (pin "2") (pinfunction "E_2") (pintype "passive"))
      (node (ref "R17") (pin "2") (pinfunction "2_2") (pintype "passive"))
      (node (ref "R19") (pin "1") (pinfunction "1_1") (pintype "passive"))
    )
    (net (code "85") (name "Net-(R8-Pad1)") (class "Default")
      (node (ref "R8") (pin "1") (pinfunction "1_1") (pintype "passive"))
      (node (ref "R9") (pin "1") (pinfunction "1_1") (pintype "passive"))
      (node (ref "TP1") (pin "1") (pinfunction "1_1") (pintype "passive"))
    )
    (net (code "86") (name "Net-(R24-Pad1)") (class "Default")
      (node (ref "R24") (pin "1") (pinfunction "1_1") (pintype "passive"))
      (node (ref "R25") (pin "2") (pinfunction "2_2") (pintype "passive"))
      (node (ref "SW*1") (pin "6") (pinfunction "6_6") (pintype "passive"))
    )
    (net (code "87") (name "Net-(R25-Pad1)") (class "Default")
      (node (ref "R25") (pin "1") (pinfunction "1_1") (pintype "passive"))
      (node (ref "R26") (pin "2") (pinfunction "2_2") (pintype "passive"))
      (node (ref "SW*1") (pin "5") (pinfunction "5_5") (pintype "passive"))
    )
    (net (code "88") (name "Net-(R26-Pad1)") (class "Default")
      (node (ref "R26") (pin "1") (pinfunction "1_1") (pintype "passive"))
      (node (ref "R27") (pin "2") (pinfunction "2_2") (pintype "passive"))
      (node (ref "SW*1") (pin "4") (pinfunction "4_4") (pintype "passive"))
    )
    (net (code "89") (name "Net-(R27-Pad1)") (class "Default")
      (node (ref "R27") (pin "1") (pinfunction "1_1") (pintype "passive"))
      (node (ref "R28") (pin "2") (pinfunction "2_2") (pintype "passive"))
      (node (ref "SW*1") (pin "3") (pinfunction "3_3") (pintype "passive"))
    )
    (net (code "90") (name "Net-(R28-Pad1)") (class "Default")
      (node (ref "R28") (pin "1") (pinfunction "1_1") (pintype "passive"))
      (node (ref "R29") (pin "2") (pinfunction "2_2") (pintype "passive"))
      (node (ref "SW*1") (pin "2") (pinfunction "2_2") (pintype "passive"))
    )
    (net (code "91") (name "Net-(U1-NRST)") (class "Default")
      (node (ref "C15") (pin "2") (pinfunction "2_2") (pintype "passive"))
      (node (ref "R13") (pin "1") (pinfunction "1_1") (pintype "passive"))
      (node (ref "SW3") (pin "2") (pinfunction "2_2") (pintype "passive"))
      (node (ref "U1") (pin "7") (pinfunction "NRST_7") (pintype "bidirectional"))
    )
    (net (code "92") (name "Net-(U2-D7)") (class "Default")
      (node (ref "C22") (pin "2") (pinfunction "2_2") (pintype "passive"))
      (node (ref "R32") (pin "1") (pinfunction "1_1") (pintype "passive"))
      (node (ref "U2") (pin "1") (pinfunction "~{OE}_1") (pintype "input"))
      (node (ref "U2") (pin "10") (pinfunction "GND_10") (pintype "power_in"))
      (node (ref "U2") (pin "18") (pinfunction "D7_18") (pintype "input"))
    )
    (net (code "93") (name "Net-(USB1-D+)") (class "Default")
      (node (ref "R3") (pin "2") (pinfunction "2_2") (pintype "passive"))
      (node (ref "USB1") (pin "3") (pinfunction "D+_3") (pintype "passive"))
    )
    (net (code "94") (name "Net-(USB1-D-)") (class "Default")
      (node (ref "R5") (pin "2") (pinfunction "2_2") (pintype "passive"))
      (node (ref "USB1") (pin "2") (pinfunction "D-_2") (pintype "passive"))
    )
    (net (code "95") (name "Net-(USB1-GND)") (class "Default")
      (node (ref "R1") (pin "2") (pinfunction "2_2") (pintype "passive"))
      (node (ref "USB1") (pin "5") (pinfunction "GND_5") (pintype "passive"))
    )
    (net (code "96") (name "V_AMS1117_3.3V_MCU") (class "Default")
      (node (ref "C10") (pin "2") (pinfunction "2_2") (pintype "passive"))
      (node (ref "C11") (pin "2") (pinfunction "2_2") (pintype "passive"))
      (node (ref "C12") (pin "2") (pinfunction "2_2") (pintype "passive"))
      (node (ref "C4") (pin "1") (pinfunction "1_1") (pintype "passive"))
      (node (ref "C5") (pin "2") (pinfunction "2_2") (pintype "passive"))
      (node (ref "C6") (pin "1") (pinfunction "1_1") (pintype "passive"))
      (node (ref "C7") (pin "2") (pinfunction "2_2") (pintype "passive"))
      (node (ref "C8") (pin "2") (pinfunction "2_2") (pintype "passive"))
      (node (ref "C9") (pin "2") (pinfunction "2_2") (pintype "passive"))
      (node (ref "JP4") (pin "3") (pinfunction "3_3") (pintype "passive"))
      (node (ref "L1") (pin "1") (pinfunction "1_1") (pintype "passive"))
      (node (ref "M1") (pin "8") (pinfunction "VCC_8") (pintype "passive"))
      (node (ref "R11") (pin "2") (pinfunction "2_2") (pintype "passive"))
      (node (ref "R13") (pin "2") (pinfunction "2_2") (pintype "passive"))
      (node (ref "R2") (pin "1") (pinfunction "1_1") (pintype "passive"))
      (node (ref "R24") (pin "2") (pinfunction "2_2") (pintype "passive"))
      (node (ref "R31") (pin "1") (pinfunction "1_1") (pintype "passive"))
      (node (ref "R4") (pin "1") (pinfunction "1_1") (pintype "passive"))
      (node (ref "U1") (pin "24") (pinfunction "VDD_1_24") (pintype "power_in"))
      (node (ref "U1") (pin "36") (pinfunction "VDD_2_36") (pintype "power_in"))
      (node (ref "U1") (pin "48") (pinfunction "VDD_3_48") (pintype "power_in"))
    )
    (net (code "97") (name "V_MCU_VDD") (class "Default")
      (node (ref "C13") (pin "2") (pinfunction "2_2") (pintype "passive"))
      (node (ref "C14") (pin "2") (pinfunction "2_2") (pintype "passive"))
      (node (ref "L1") (pin "2") (pinfunction "2_2") (pintype "passive"))
      (node (ref "U1") (pin "9") (pinfunction "VDDA_9") (pintype "power_in"))
    )
    (net (code "98") (name "V_TPS5450_5V") (class "Default")
      (node (ref "C21") (pin "2") (pinfunction "2_2") (pintype "passive"))
      (node (ref "C22") (pin "1") (pinfunction "1_1") (pintype "passive"))
      (node (ref "D1") (pin "2") (pinfunction "K_2") (pintype "passive"))
      (node (ref "D2") (pin "1") (pinfunction "A_1") (pintype "passive"))
      (node (ref "F1") (pin "2") (pinfunction "2_2") (pintype "passive"))
      (node (ref "IC1") (pin "7") (pinfunction "V+_7") (pintype "power_in"))
      (node (ref "L2") (pin "1") (pinfunction "1_1") (pintype "passive"))
      (node (ref "LS1") (pin "1") (pinfunction "1_1") (pintype "passive"))
      (node (ref "R7") (pin "2") (pinfunction "2_2") (pintype "passive"))
      (node (ref "U2") (pin "20") (pinfunction "VCC_20") (pintype "power_in"))
    )
    (net (code "99") (name "unconnected-(IC1-Pad1)") (class "Default")
      (node (ref "IC1") (pin "1") (pinfunction "1_1") (pintype "passive+no_connect"))
    )
    (net (code "100") (name "unconnected-(IC1-Pad8)") (class "Default")
      (node (ref "IC1") (pin "8") (pinfunction "8_8") (pintype "passive+no_connect"))
    )
    (net (code "101") (name "unconnected-(JP5-Pad1)") (class "Default")
      (node (ref "JP5") (pin "1") (pinfunction "1_1") (pintype "passive"))
    )
    (net (code "102") (name "unconnected-(JP6-Pad7)") (class "Default")
      (node (ref "JP6") (pin "7") (pinfunction "7_7") (pintype "passive"))
    )
    (net (code "103") (name "unconnected-(JP6-Pad8)") (class "Default")
      (node (ref "JP6") (pin "8") (pinfunction "8_8") (pintype "passive"))
    )
    (net (code "104") (name "unconnected-(JP6.-Pad1)") (class "Default")
      (node (ref "JP6.") (pin "1") (pinfunction "1_1") (pintype "passive"))
    )
    (net (code "105") (name "unconnected-(JP6.-Pad2)") (class "Default")
      (node (ref "JP6.") (pin "2") (pinfunction "2_2") (pintype "passive"))
    )
    (net (code "106") (name "unconnected-(JP7-Pad1)") (class "Default")
      (node (ref "JP7") (pin "1") (pinfunction "1_1") (pintype "passive"))
    )
    (net (code "107") (name "unconnected-(JP7-Pad2)") (class "Default")
      (node (ref "JP7") (pin "2") (pinfunction "2_2") (pintype "passive"))
    )
    (net (code "108") (name "unconnected-(M1-GPIO2-Pad11)") (class "Default")
      (node (ref "M1") (pin "11") (pinfunction "GPIO2_11") (pintype "passive+no_connect"))
    )
    (net (code "109") (name "unconnected-(U2-Q7-Pad19)") (class "Default")
      (node (ref "U2") (pin "19") (pinfunction "Q7_19") (pintype "tri_state+no_connect"))
    )
    (net (code "110") (name "unconnected-(USB1-ID-Pad4)") (class "Default")
      (node (ref "USB1") (pin "4") (pinfunction "ID_4") (pintype "passive+no_connect"))
    )
  )
)
